# SDRAM.net
KiCad netlist of a schematic drawn in Altium Designer
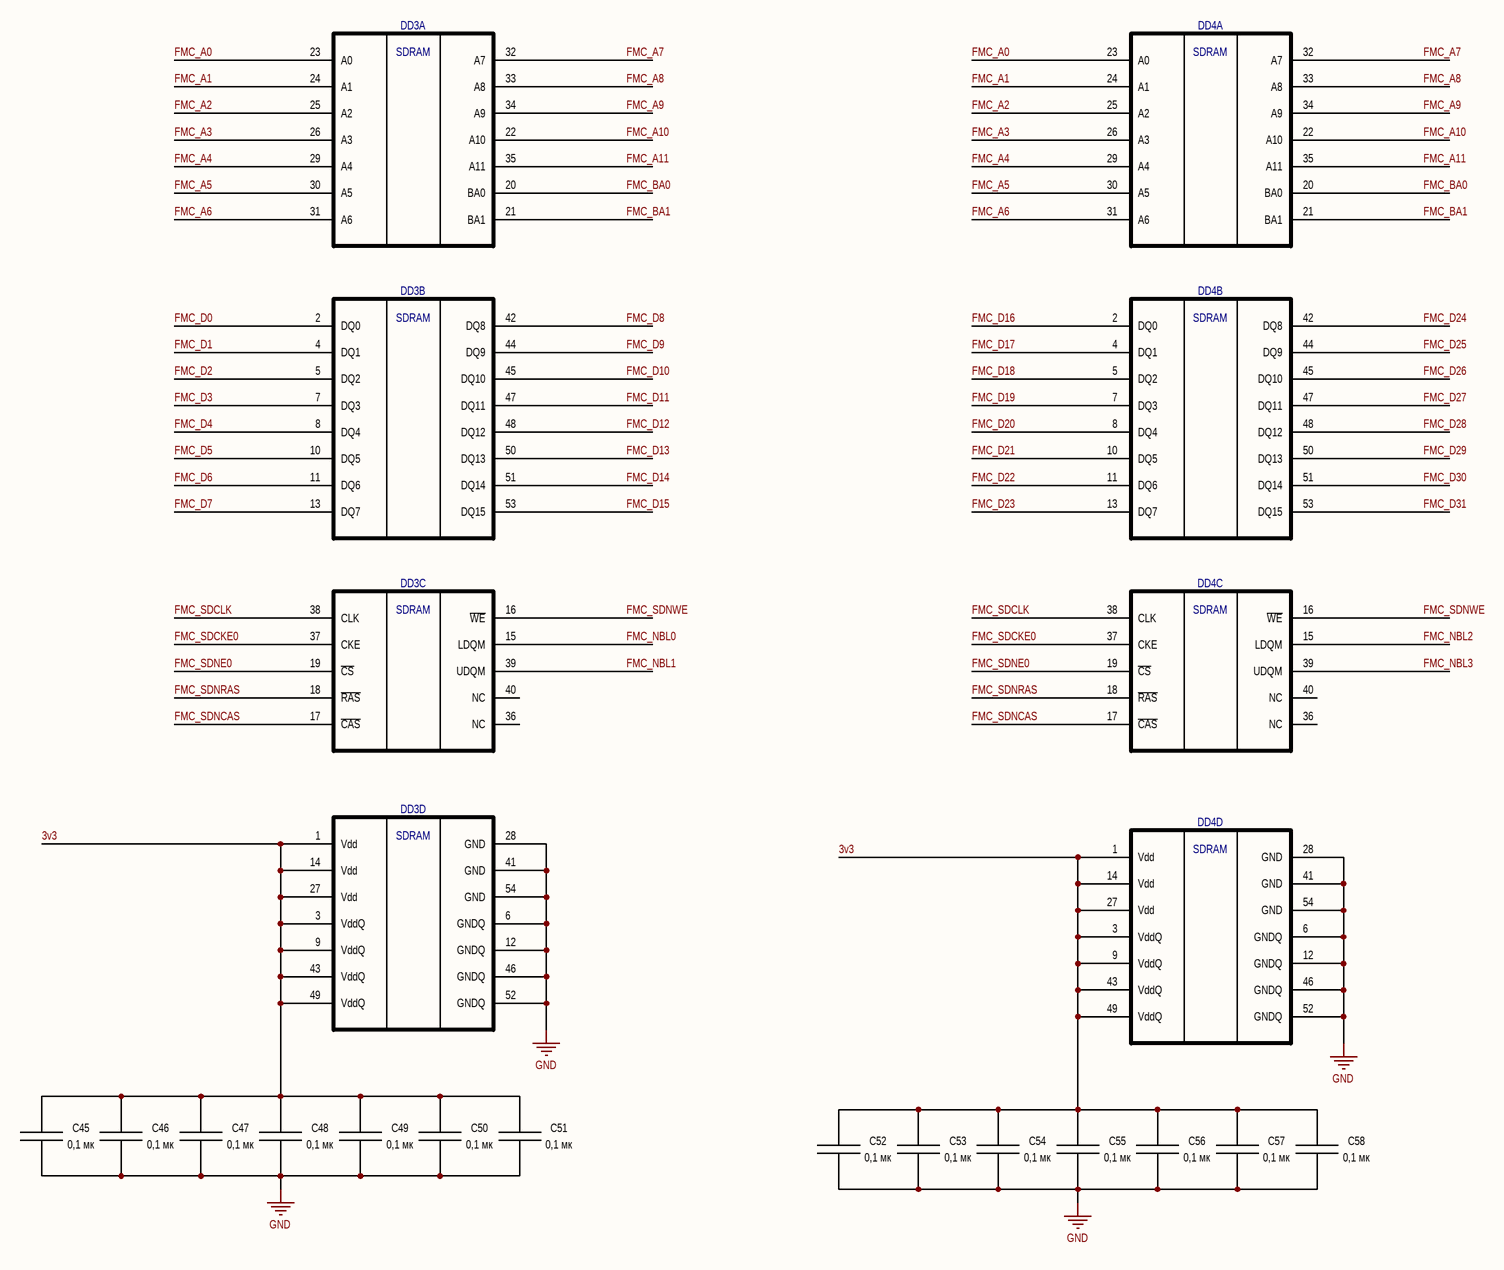
[diagram p0: SDRAM.SchDoc]

(export (version "E")
  (design (tool "Eeschema 10.0.6"))
  (components
    (comp (ref "C45")
      (value "0,1 мк")
      (footprint "C0603")
      (fields
        (field (name "TOLERANCE") "±10%")
        (field (name "VOLTAGE") "50 В")
        (field (name "PARTNUMBER") "GRM188R71H104KA93D")
      )
      (libsource (lib "5ko") (part "C"))
    )
    (comp (ref "C46")
      (value "0,1 мк")
      (footprint "C0603")
      (fields
        (field (name "TOLERANCE") "±10%")
        (field (name "VOLTAGE") "50 В")
        (field (name "PARTNUMBER") "GRM188R71H104KA93D")
      )
      (libsource (lib "5ko") (part "C"))
    )
    (comp (ref "C47")
      (value "0,1 мк")
      (footprint "C0603")
      (fields
        (field (name "TOLERANCE") "±10%")
        (field (name "VOLTAGE") "50 В")
        (field (name "PARTNUMBER") "GRM188R71H104KA93D")
      )
      (libsource (lib "5ko") (part "C"))
    )
    (comp (ref "C48")
      (value "0,1 мк")
      (footprint "C0603")
      (fields
        (field (name "TOLERANCE") "±10%")
        (field (name "VOLTAGE") "50 В")
        (field (name "PARTNUMBER") "GRM188R71H104KA93D")
      )
      (libsource (lib "5ko") (part "C"))
    )
    (comp (ref "C49")
      (value "0,1 мк")
      (footprint "C0603")
      (fields
        (field (name "TOLERANCE") "±10%")
        (field (name "VOLTAGE") "50 В")
        (field (name "PARTNUMBER") "GRM188R71H104KA93D")
      )
      (libsource (lib "5ko") (part "C"))
    )
    (comp (ref "C50")
      (value "0,1 мк")
      (footprint "C0603")
      (fields
        (field (name "TOLERANCE") "±10%")
        (field (name "VOLTAGE") "50 В")
        (field (name "PARTNUMBER") "GRM188R71H104KA93D")
      )
      (libsource (lib "5ko") (part "C"))
    )
    (comp (ref "C51")
      (value "0,1 мк")
      (footprint "C0603")
      (fields
        (field (name "TOLERANCE") "±10%")
        (field (name "VOLTAGE") "50 В")
        (field (name "PARTNUMBER") "GRM188R71H104KA93D")
      )
      (libsource (lib "5ko") (part "C"))
    )
    (comp (ref "C52")
      (value "0,1 мк")
      (footprint "C0603")
      (fields
        (field (name "TOLERANCE") "±10%")
        (field (name "VOLTAGE") "50 В")
        (field (name "PARTNUMBER") "GRM188R71H104KA93D")
      )
      (libsource (lib "5ko") (part "C"))
    )
    (comp (ref "C53")
      (value "0,1 мк")
      (footprint "C0603")
      (fields
        (field (name "TOLERANCE") "±10%")
        (field (name "VOLTAGE") "50 В")
        (field (name "PARTNUMBER") "GRM188R71H104KA93D")
      )
      (libsource (lib "5ko") (part "C"))
    )
    (comp (ref "C54")
      (value "0,1 мк")
      (footprint "C0603")
      (fields
        (field (name "TOLERANCE") "±10%")
        (field (name "VOLTAGE") "50 В")
        (field (name "PARTNUMBER") "GRM188R71H104KA93D")
      )
      (libsource (lib "5ko") (part "C"))
    )
    (comp (ref "C55")
      (value "0,1 мк")
      (footprint "C0603")
      (fields
        (field (name "TOLERANCE") "±10%")
        (field (name "VOLTAGE") "50 В")
        (field (name "PARTNUMBER") "GRM188R71H104KA93D")
      )
      (libsource (lib "5ko") (part "C"))
    )
    (comp (ref "C56")
      (value "0,1 мк")
      (footprint "C0603")
      (fields
        (field (name "TOLERANCE") "±10%")
        (field (name "VOLTAGE") "50 В")
        (field (name "PARTNUMBER") "GRM188R71H104KA93D")
      )
      (libsource (lib "5ko") (part "C"))
    )
    (comp (ref "C57")
      (value "0,1 мк")
      (footprint "C0603")
      (fields
        (field (name "TOLERANCE") "±10%")
        (field (name "VOLTAGE") "50 В")
        (field (name "PARTNUMBER") "GRM188R71H104KA93D")
      )
      (libsource (lib "5ko") (part "C"))
    )
    (comp (ref "C58")
      (value "0,1 мк")
      (footprint "C0603")
      (fields
        (field (name "TOLERANCE") "±10%")
        (field (name "VOLTAGE") "50 В")
        (field (name "PARTNUMBER") "GRM188R71H104KA93D")
      )
      (libsource (lib "5ko") (part "C"))
    )
    (comp (ref "DD3")
      (value "IS42S16400J")
      (footprint "TSOP-54")
      (libsource (lib "5ko") (part "IS42S16400J"))
    )
    (comp (ref "DD4")
      (value "IS42S16400J")
      (footprint "TSOP-54")
      (libsource (lib "5ko") (part "IS42S16400J"))
    )
  )
  (nets
    (net (code "1") (name "/3v3") (class "Default")
      (node (ref "C45") (pin "1") (pinfunction "1_1") (pintype "passive"))
      (node (ref "C46") (pin "1") (pinfunction "1_1") (pintype "passive"))
      (node (ref "C47") (pin "1") (pinfunction "1_1") (pintype "passive"))
      (node (ref "C48") (pin "1") (pinfunction "1_1") (pintype "passive"))
      (node (ref "C49") (pin "1") (pinfunction "1_1") (pintype "passive"))
      (node (ref "C50") (pin "1") (pinfunction "1_1") (pintype "passive"))
      (node (ref "C51") (pin "1") (pinfunction "1_1") (pintype "passive"))
      (node (ref "C52") (pin "1") (pinfunction "1_1") (pintype "passive"))
      (node (ref "C53") (pin "1") (pinfunction "1_1") (pintype "passive"))
      (node (ref "C54") (pin "1") (pinfunction "1_1") (pintype "passive"))
      (node (ref "C55") (pin "1") (pinfunction "1_1") (pintype "passive"))
      (node (ref "C56") (pin "1") (pinfunction "1_1") (pintype "passive"))
      (node (ref "C57") (pin "1") (pinfunction "1_1") (pintype "passive"))
      (node (ref "C58") (pin "1") (pinfunction "1_1") (pintype "passive"))
      (node (ref "DD3") (pin "1") (pinfunction "Vdd_1") (pintype "passive"))
      (node (ref "DD3") (pin "14") (pinfunction "Vdd_14") (pintype "passive"))
      (node (ref "DD3") (pin "27") (pinfunction "Vdd_27") (pintype "passive"))
      (node (ref "DD3") (pin "3") (pinfunction "VddQ_3") (pintype "passive"))
      (node (ref "DD3") (pin "43") (pinfunction "VddQ_43") (pintype "passive"))
      (node (ref "DD3") (pin "49") (pinfunction "VddQ_49") (pintype "passive"))
      (node (ref "DD3") (pin "9") (pinfunction "VddQ_9") (pintype "passive"))
      (node (ref "DD4") (pin "1") (pinfunction "Vdd_1") (pintype "passive"))
      (node (ref "DD4") (pin "14") (pinfunction "Vdd_14") (pintype "passive"))
      (node (ref "DD4") (pin "27") (pinfunction "Vdd_27") (pintype "passive"))
      (node (ref "DD4") (pin "3") (pinfunction "VddQ_3") (pintype "passive"))
      (node (ref "DD4") (pin "43") (pinfunction "VddQ_43") (pintype "passive"))
      (node (ref "DD4") (pin "49") (pinfunction "VddQ_49") (pintype "passive"))
      (node (ref "DD4") (pin "9") (pinfunction "VddQ_9") (pintype "passive"))
    )
    (net (code "2") (name "/FMC_A0") (class "Default")
      (node (ref "DD3") (pin "23") (pinfunction "A0_23") (pintype "passive"))
      (node (ref "DD4") (pin "23") (pinfunction "A0_23") (pintype "passive"))
    )
    (net (code "3") (name "/FMC_A1") (class "Default")
      (node (ref "DD3") (pin "24") (pinfunction "A1_24") (pintype "passive"))
      (node (ref "DD4") (pin "24") (pinfunction "A1_24") (pintype "passive"))
    )
    (net (code "4") (name "/FMC_A2") (class "Default")
      (node (ref "DD3") (pin "25") (pinfunction "A2_25") (pintype "passive"))
      (node (ref "DD4") (pin "25") (pinfunction "A2_25") (pintype "passive"))
    )
    (net (code "5") (name "/FMC_A3") (class "Default")
      (node (ref "DD3") (pin "26") (pinfunction "A3_26") (pintype "passive"))
      (node (ref "DD4") (pin "26") (pinfunction "A3_26") (pintype "passive"))
    )
    (net (code "6") (name "/FMC_A4") (class "Default")
      (node (ref "DD3") (pin "29") (pinfunction "A4_29") (pintype "passive"))
      (node (ref "DD4") (pin "29") (pinfunction "A4_29") (pintype "passive"))
    )
    (net (code "7") (name "/FMC_A5") (class "Default")
      (node (ref "DD3") (pin "30") (pinfunction "A5_30") (pintype "passive"))
      (node (ref "DD4") (pin "30") (pinfunction "A5_30") (pintype "passive"))
    )
    (net (code "8") (name "/FMC_A6") (class "Default")
      (node (ref "DD3") (pin "31") (pinfunction "A6_31") (pintype "passive"))
      (node (ref "DD4") (pin "31") (pinfunction "A6_31") (pintype "passive"))
    )
    (net (code "9") (name "/FMC_A7") (class "Default")
      (node (ref "DD3") (pin "32") (pinfunction "A7_32") (pintype "passive"))
      (node (ref "DD4") (pin "32") (pinfunction "A7_32") (pintype "passive"))
    )
    (net (code "10") (name "/FMC_A8") (class "Default")
      (node (ref "DD3") (pin "33") (pinfunction "A8_33") (pintype "passive"))
      (node (ref "DD4") (pin "33") (pinfunction "A8_33") (pintype "passive"))
    )
    (net (code "11") (name "/FMC_A9") (class "Default")
      (node (ref "DD3") (pin "34") (pinfunction "A9_34") (pintype "passive"))
      (node (ref "DD4") (pin "34") (pinfunction "A9_34") (pintype "passive"))
    )
    (net (code "12") (name "/FMC_A10") (class "Default")
      (node (ref "DD3") (pin "22") (pinfunction "A10_22") (pintype "passive"))
      (node (ref "DD4") (pin "22") (pinfunction "A10_22") (pintype "passive"))
    )
    (net (code "13") (name "/FMC_A11") (class "Default")
      (node (ref "DD3") (pin "35") (pinfunction "A11_35") (pintype "passive"))
      (node (ref "DD4") (pin "35") (pinfunction "A11_35") (pintype "passive"))
    )
    (net (code "14") (name "/FMC_BA0") (class "Default")
      (node (ref "DD3") (pin "20") (pinfunction "BA0_20") (pintype "passive"))
      (node (ref "DD4") (pin "20") (pinfunction "BA0_20") (pintype "passive"))
    )
    (net (code "15") (name "/FMC_BA1") (class "Default")
      (node (ref "DD3") (pin "21") (pinfunction "BA1_21") (pintype "passive"))
      (node (ref "DD4") (pin "21") (pinfunction "BA1_21") (pintype "passive"))
    )
    (net (code "16") (name "/FMC_D0") (class "Default")
      (node (ref "DD3") (pin "2") (pinfunction "DQ0_2") (pintype "passive"))
    )
    (net (code "17") (name "/FMC_D1") (class "Default")
      (node (ref "DD3") (pin "4") (pinfunction "DQ1_4") (pintype "passive"))
    )
    (net (code "18") (name "/FMC_D2") (class "Default")
      (node (ref "DD3") (pin "5") (pinfunction "DQ2_5") (pintype "passive"))
    )
    (net (code "19") (name "/FMC_D3") (class "Default")
      (node (ref "DD3") (pin "7") (pinfunction "DQ3_7") (pintype "passive"))
    )
    (net (code "20") (name "/FMC_D4") (class "Default")
      (node (ref "DD3") (pin "8") (pinfunction "DQ4_8") (pintype "passive"))
    )
    (net (code "21") (name "/FMC_D5") (class "Default")
      (node (ref "DD3") (pin "10") (pinfunction "DQ5_10") (pintype "passive"))
    )
    (net (code "22") (name "/FMC_D6") (class "Default")
      (node (ref "DD3") (pin "11") (pinfunction "DQ6_11") (pintype "passive"))
    )
    (net (code "23") (name "/FMC_D7") (class "Default")
      (node (ref "DD3") (pin "13") (pinfunction "DQ7_13") (pintype "passive"))
    )
    (net (code "24") (name "/FMC_D8") (class "Default")
      (node (ref "DD3") (pin "42") (pinfunction "DQ8_42") (pintype "passive"))
    )
    (net (code "25") (name "/FMC_D9") (class "Default")
      (node (ref "DD3") (pin "44") (pinfunction "DQ9_44") (pintype "passive"))
    )
    (net (code "26") (name "/FMC_D10") (class "Default")
      (node (ref "DD3") (pin "45") (pinfunction "DQ10_45") (pintype "passive"))
    )
    (net (code "27") (name "/FMC_D11") (class "Default")
      (node (ref "DD3") (pin "47") (pinfunction "DQ11_47") (pintype "passive"))
    )
    (net (code "28") (name "/FMC_D12") (class "Default")
      (node (ref "DD3") (pin "48") (pinfunction "DQ12_48") (pintype "passive"))
    )
    (net (code "29") (name "/FMC_D13") (class "Default")
      (node (ref "DD3") (pin "50") (pinfunction "DQ13_50") (pintype "passive"))
    )
    (net (code "30") (name "/FMC_D14") (class "Default")
      (node (ref "DD3") (pin "51") (pinfunction "DQ14_51") (pintype "passive"))
    )
    (net (code "31") (name "/FMC_D15") (class "Default")
      (node (ref "DD3") (pin "53") (pinfunction "DQ15_53") (pintype "passive"))
    )
    (net (code "32") (name "/FMC_D16") (class "Default")
      (node (ref "DD4") (pin "2") (pinfunction "DQ0_2") (pintype "passive"))
    )
    (net (code "33") (name "/FMC_D17") (class "Default")
      (node (ref "DD4") (pin "4") (pinfunction "DQ1_4") (pintype "passive"))
    )
    (net (code "34") (name "/FMC_D18") (class "Default")
      (node (ref "DD4") (pin "5") (pinfunction "DQ2_5") (pintype "passive"))
    )
    (net (code "35") (name "/FMC_D19") (class "Default")
      (node (ref "DD4") (pin "7") (pinfunction "DQ3_7") (pintype "passive"))
    )
    (net (code "36") (name "/FMC_D20") (class "Default")
      (node (ref "DD4") (pin "8") (pinfunction "DQ4_8") (pintype "passive"))
    )
    (net (code "37") (name "/FMC_D21") (class "Default")
      (node (ref "DD4") (pin "10") (pinfunction "DQ5_10") (pintype "passive"))
    )
    (net (code "38") (name "/FMC_D22") (class "Default")
      (node (ref "DD4") (pin "11") (pinfunction "DQ6_11") (pintype "passive"))
    )
    (net (code "39") (name "/FMC_D23") (class "Default")
      (node (ref "DD4") (pin "13") (pinfunction "DQ7_13") (pintype "passive"))
    )
    (net (code "40") (name "/FMC_D24") (class "Default")
      (node (ref "DD4") (pin "42") (pinfunction "DQ8_42") (pintype "passive"))
    )
    (net (code "41") (name "/FMC_D25") (class "Default")
      (node (ref "DD4") (pin "44") (pinfunction "DQ9_44") (pintype "passive"))
    )
    (net (code "42") (name "/FMC_D26") (class "Default")
      (node (ref "DD4") (pin "45") (pinfunction "DQ10_45") (pintype "passive"))
    )
    (net (code "43") (name "/FMC_D27") (class "Default")
      (node (ref "DD4") (pin "47") (pinfunction "DQ11_47") (pintype "passive"))
    )
    (net (code "44") (name "/FMC_D28") (class "Default")
      (node (ref "DD4") (pin "48") (pinfunction "DQ12_48") (pintype "passive"))
    )
    (net (code "45") (name "/FMC_D29") (class "Default")
      (node (ref "DD4") (pin "50") (pinfunction "DQ13_50") (pintype "passive"))
    )
    (net (code "46") (name "/FMC_D30") (class "Default")
      (node (ref "DD4") (pin "51") (pinfunction "DQ14_51") (pintype "passive"))
    )
    (net (code "47") (name "/FMC_D31") (class "Default")
      (node (ref "DD4") (pin "53") (pinfunction "DQ15_53") (pintype "passive"))
    )
    (net (code "48") (name "/FMC_NBL0") (class "Default")
      (node (ref "DD3") (pin "15") (pinfunction "LDQM_15") (pintype "passive"))
    )
    (net (code "49") (name "/FMC_NBL1") (class "Default")
      (node (ref "DD3") (pin "39") (pinfunction "UDQM_39") (pintype "passive"))
    )
    (net (code "50") (name "/FMC_NBL2") (class "Default")
      (node (ref "DD4") (pin "15") (pinfunction "LDQM_15") (pintype "passive"))
    )
    (net (code "51") (name "/FMC_NBL3") (class "Default")
      (node (ref "DD4") (pin "39") (pinfunction "UDQM_39") (pintype "passive"))
    )
    (net (code "52") (name "/FMC_SDCKE0") (class "Default")
      (node (ref "DD3") (pin "37") (pinfunction "CKE_37") (pintype "passive"))
      (node (ref "DD4") (pin "37") (pinfunction "CKE_37") (pintype "passive"))
    )
    (net (code "53") (name "/FMC_SDCLK") (class "Default")
      (node (ref "DD3") (pin "38") (pinfunction "CLK_38") (pintype "passive"))
      (node (ref "DD4") (pin "38") (pinfunction "CLK_38") (pintype "passive"))
    )
    (net (code "54") (name "/FMC_SDNCAS") (class "Default")
      (node (ref "DD3") (pin "17") (pinfunction "~{CAS}_17") (pintype "passive"))
      (node (ref "DD4") (pin "17") (pinfunction "~{CAS}_17") (pintype "passive"))
    )
    (net (code "55") (name "/FMC_SDNE0") (class "Default")
      (node (ref "DD3") (pin "19") (pinfunction "~{CS}_19") (pintype "passive"))
      (node (ref "DD4") (pin "19") (pinfunction "~{CS}_19") (pintype "passive"))
    )
    (net (code "56") (name "/FMC_SDNRAS") (class "Default")
      (node (ref "DD3") (pin "18") (pinfunction "~{RAS}_18") (pintype "passive"))
      (node (ref "DD4") (pin "18") (pinfunction "~{RAS}_18") (pintype "passive"))
    )
    (net (code "57") (name "/FMC_SDNWE") (class "Default")
      (node (ref "DD3") (pin "16") (pinfunction "~{WE}_16") (pintype "passive"))
      (node (ref "DD4") (pin "16") (pinfunction "~{WE}_16") (pintype "passive"))
    )
    (net (code "58") (name "GND") (class "Default")
      (node (ref "C45") (pin "2") (pinfunction "2_2") (pintype "passive"))
      (node (ref "C46") (pin "2") (pinfunction "2_2") (pintype "passive"))
      (node (ref "C47") (pin "2") (pinfunction "2_2") (pintype "passive"))
      (node (ref "C48") (pin "2") (pinfunction "2_2") (pintype "passive"))
      (node (ref "C49") (pin "2") (pinfunction "2_2") (pintype "passive"))
      (node (ref "C50") (pin "2") (pinfunction "2_2") (pintype "passive"))
      (node (ref "C51") (pin "2") (pinfunction "2_2") (pintype "passive"))
      (node (ref "C52") (pin "2") (pinfunction "2_2") (pintype "passive"))
      (node (ref "C53") (pin "2") (pinfunction "2_2") (pintype "passive"))
      (node (ref "C54") (pin "2") (pinfunction "2_2") (pintype "passive"))
      (node (ref "C55") (pin "2") (pinfunction "2_2") (pintype "passive"))
      (node (ref "C56") (pin "2") (pinfunction "2_2") (pintype "passive"))
      (node (ref "C57") (pin "2") (pinfunction "2_2") (pintype "passive"))
      (node (ref "C58") (pin "2") (pinfunction "2_2") (pintype "passive"))
      (node (ref "DD3") (pin "12") (pinfunction "GNDQ_12") (pintype "passive"))
      (node (ref "DD3") (pin "28") (pinfunction "GND_28") (pintype "passive"))
      (node (ref "DD3") (pin "41") (pinfunction "GND_41") (pintype "passive"))
      (node (ref "DD3") (pin "46") (pinfunction "GNDQ_46") (pintype "passive"))
      (node (ref "DD3") (pin "52") (pinfunction "GNDQ_52") (pintype "passive"))
      (node (ref "DD3") (pin "54") (pinfunction "GND_54") (pintype "passive"))
      (node (ref "DD3") (pin "6") (pinfunction "GNDQ_6") (pintype "passive"))
      (node (ref "DD4") (pin "12") (pinfunction "GNDQ_12") (pintype "passive"))
      (node (ref "DD4") (pin "28") (pinfunction "GND_28") (pintype "passive"))
      (node (ref "DD4") (pin "41") (pinfunction "GND_41") (pintype "passive"))
      (node (ref "DD4") (pin "46") (pinfunction "GNDQ_46") (pintype "passive"))
      (node (ref "DD4") (pin "52") (pinfunction "GNDQ_52") (pintype "passive"))
      (node (ref "DD4") (pin "54") (pinfunction "GND_54") (pintype "passive"))
      (node (ref "DD4") (pin "6") (pinfunction "GNDQ_6") (pintype "passive"))
    )
    (net (code "59") (name "unconnected-(DD3C-NC-Pad36)") (class "Default")
      (node (ref "DD3") (pin "36") (pinfunction "NC_36") (pintype "passive"))
    )
    (net (code "60") (name "unconnected-(DD3C-NC-Pad40)") (class "Default")
      (node (ref "DD3") (pin "40") (pinfunction "NC_40") (pintype "passive"))
    )
    (net (code "61") (name "unconnected-(DD4C-NC-Pad36)") (class "Default")
      (node (ref "DD4") (pin "36") (pinfunction "NC_36") (pintype "passive"))
    )
    (net (code "62") (name "unconnected-(DD4C-NC-Pad40)") (class "Default")
      (node (ref "DD4") (pin "40") (pinfunction "NC_40") (pintype "passive"))
    )
  )
)
